# seedrum_relay_v1.net
KiCad netlist of a schematic drawn in EasyEDA
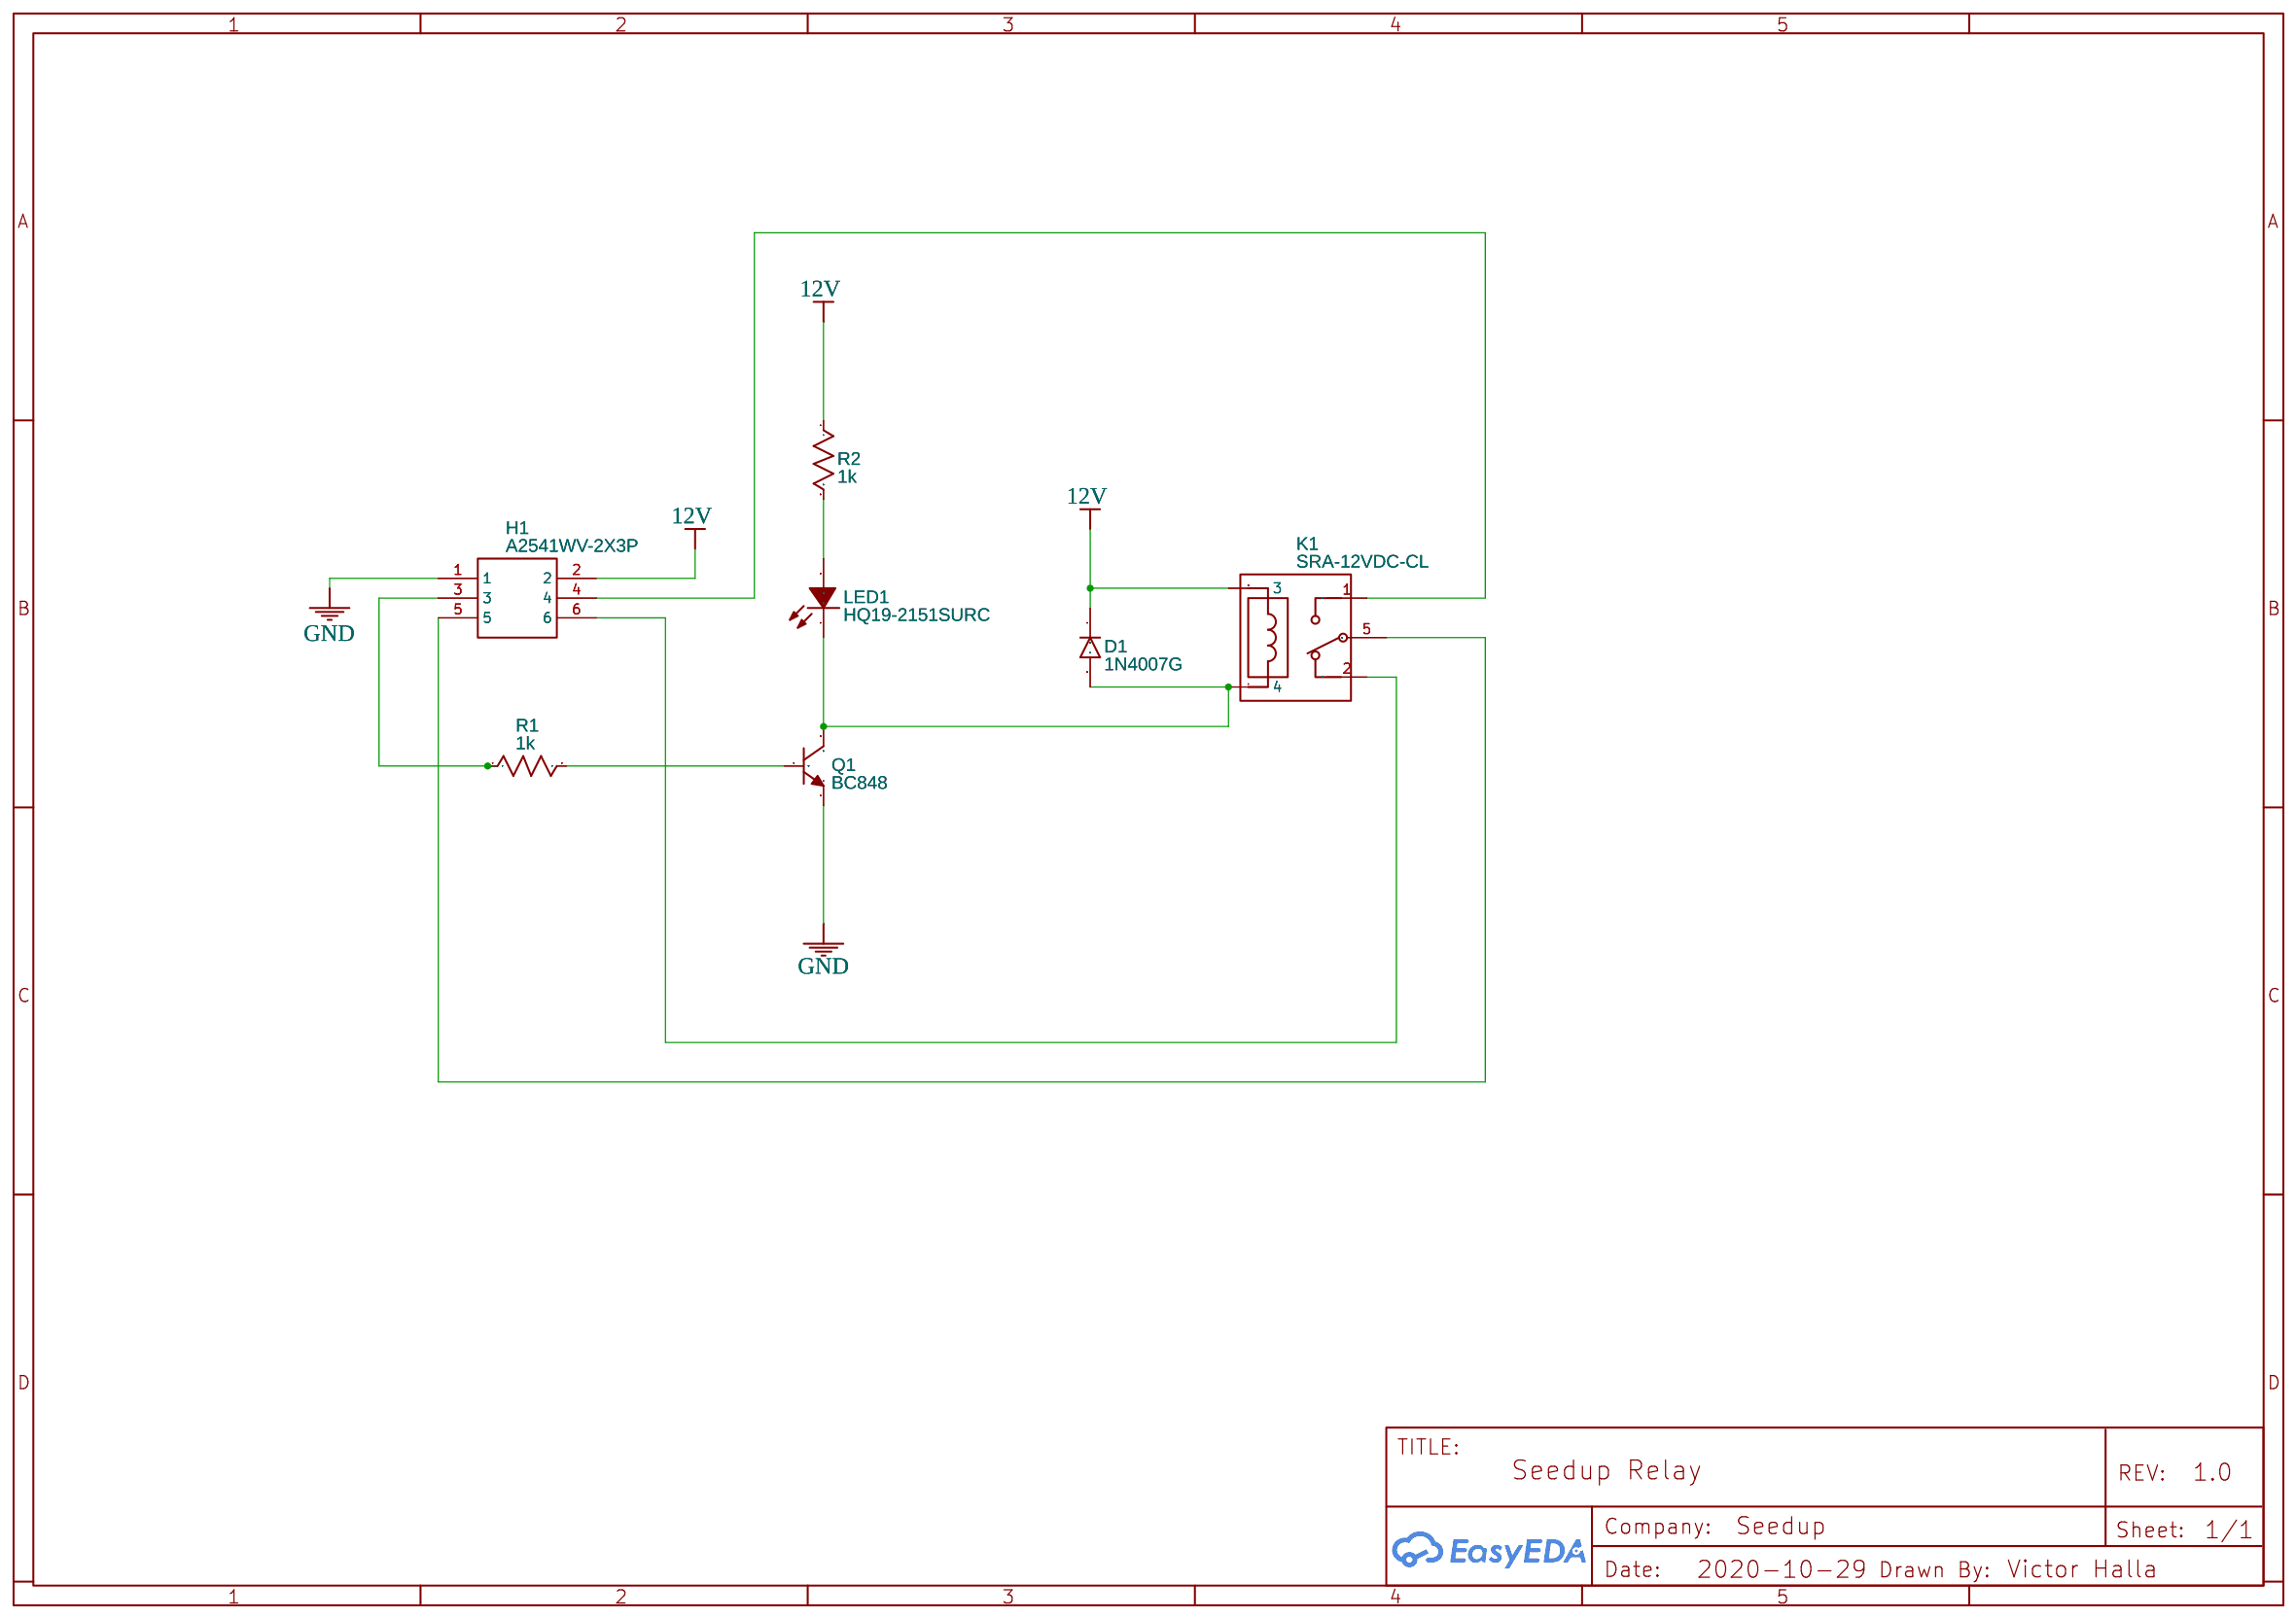
[diagram p0: schematic sheet]

(export (version "E")
  (design (tool "Eeschema 10.0.6"))
  (components
    (comp (ref "D1")
      (value "1N4007G")
      (fields (field (name "BOM_Supplier Part") "C111122"))
      (libsource (lib "") (part "1N4007G"))
    )
    (comp (ref "H1")
      (value "A2541WV-2X3P")
      (fields
        (field (name "BOM_Manufacturer Part") "A2541WV-2x3P")
        (field (name "BOM_Supplier Part") "C225518")
      )
      (libsource (lib "") (part "A2541WV-2X3P"))
    )
    (comp (ref "K1")
      (value "SRA-12VDC-CL")
      (fields (field (name "BOM_Supplier Part") "C60169"))
      (libsource (lib "") (part "SRA-12VDC-CL"))
    )
    (comp (ref "LED1")
      (value "HQ19-2151SURC")
      (fields (field (name "BOM_Supplier Part") "C258842"))
      (libsource (lib "") (part "HQ19-2151SURC"))
    )
    (comp (ref "Q1")
      (value "BC848")
      (fields (field (name "BOM_Supplier Part") "C692844"))
      (libsource (lib "") (part "BC848"))
    )
    (comp (ref "R1") (value "1k") (libsource (lib "") (part "R_0603_US")))
    (comp (ref "R2") (value "1k") (libsource (lib "") (part "R_0603_US_1")))
  )
  (nets
    (net (code "1") (name "12V") (class "Default")
      (node (ref "D1") (pin "1") (pinfunction "C_1") (pintype "unspecified"))
      (node (ref "H1") (pin "2") (pinfunction "2_2") (pintype "unspecified"))
      (node (ref "K1") (pin "3") (pinfunction "3_3") (pintype "unspecified"))
      (node (ref "R2") (pin "1") (pinfunction "1_1") (pintype "unspecified"))
    )
    (net (code "2") (name "GND") (class "Default")
      (node (ref "H1") (pin "1") (pinfunction "1_1") (pintype "unspecified"))
      (node (ref "Q1") (pin "2") (pinfunction "E_2") (pintype "input"))
    )
    (net (code "3") (name "Net-(D1-A)") (class "Default")
      (node (ref "D1") (pin "2") (pinfunction "A_2") (pintype "unspecified"))
      (node (ref "K1") (pin "4") (pinfunction "4_4") (pintype "unspecified"))
      (node (ref "LED1") (pin "1") (pinfunction "K_1") (pintype "unspecified"))
      (node (ref "Q1") (pin "3") (pinfunction "C_3") (pintype "input"))
    )
    (net (code "4") (name "Net-(H1-Pad3)") (class "Default")
      (node (ref "H1") (pin "3") (pinfunction "3_3") (pintype "unspecified"))
      (node (ref "R1") (pin "1") (pinfunction "1_1") (pintype "unspecified"))
    )
    (net (code "5") (name "Net-(H1-Pad4)") (class "Default")
      (node (ref "H1") (pin "4") (pinfunction "4_4") (pintype "unspecified"))
      (node (ref "K1") (pin "1") (pinfunction "1_1") (pintype "unspecified"))
    )
    (net (code "6") (name "Net-(H1-Pad5)") (class "Default")
      (node (ref "H1") (pin "5") (pinfunction "5_5") (pintype "unspecified"))
      (node (ref "K1") (pin "5") (pinfunction "5_5") (pintype "unspecified"))
    )
    (net (code "7") (name "Net-(H1-Pad6)") (class "Default")
      (node (ref "H1") (pin "6") (pinfunction "6_6") (pintype "unspecified"))
      (node (ref "K1") (pin "2") (pinfunction "2_2") (pintype "unspecified"))
    )
    (net (code "8") (name "Net-(LED1-A)") (class "Default")
      (node (ref "LED1") (pin "2") (pinfunction "A_2") (pintype "unspecified"))
      (node (ref "R2") (pin "2") (pinfunction "2_2") (pintype "unspecified"))
    )
    (net (code "9") (name "Net-(Q1-B)") (class "Default")
      (node (ref "Q1") (pin "1") (pinfunction "B_1") (pintype "input"))
      (node (ref "R1") (pin "2") (pinfunction "2_2") (pintype "unspecified"))
    )
  )
)
